# Power_28_10_15_v7.net
KiCad netlist of a schematic drawn in EAGLE
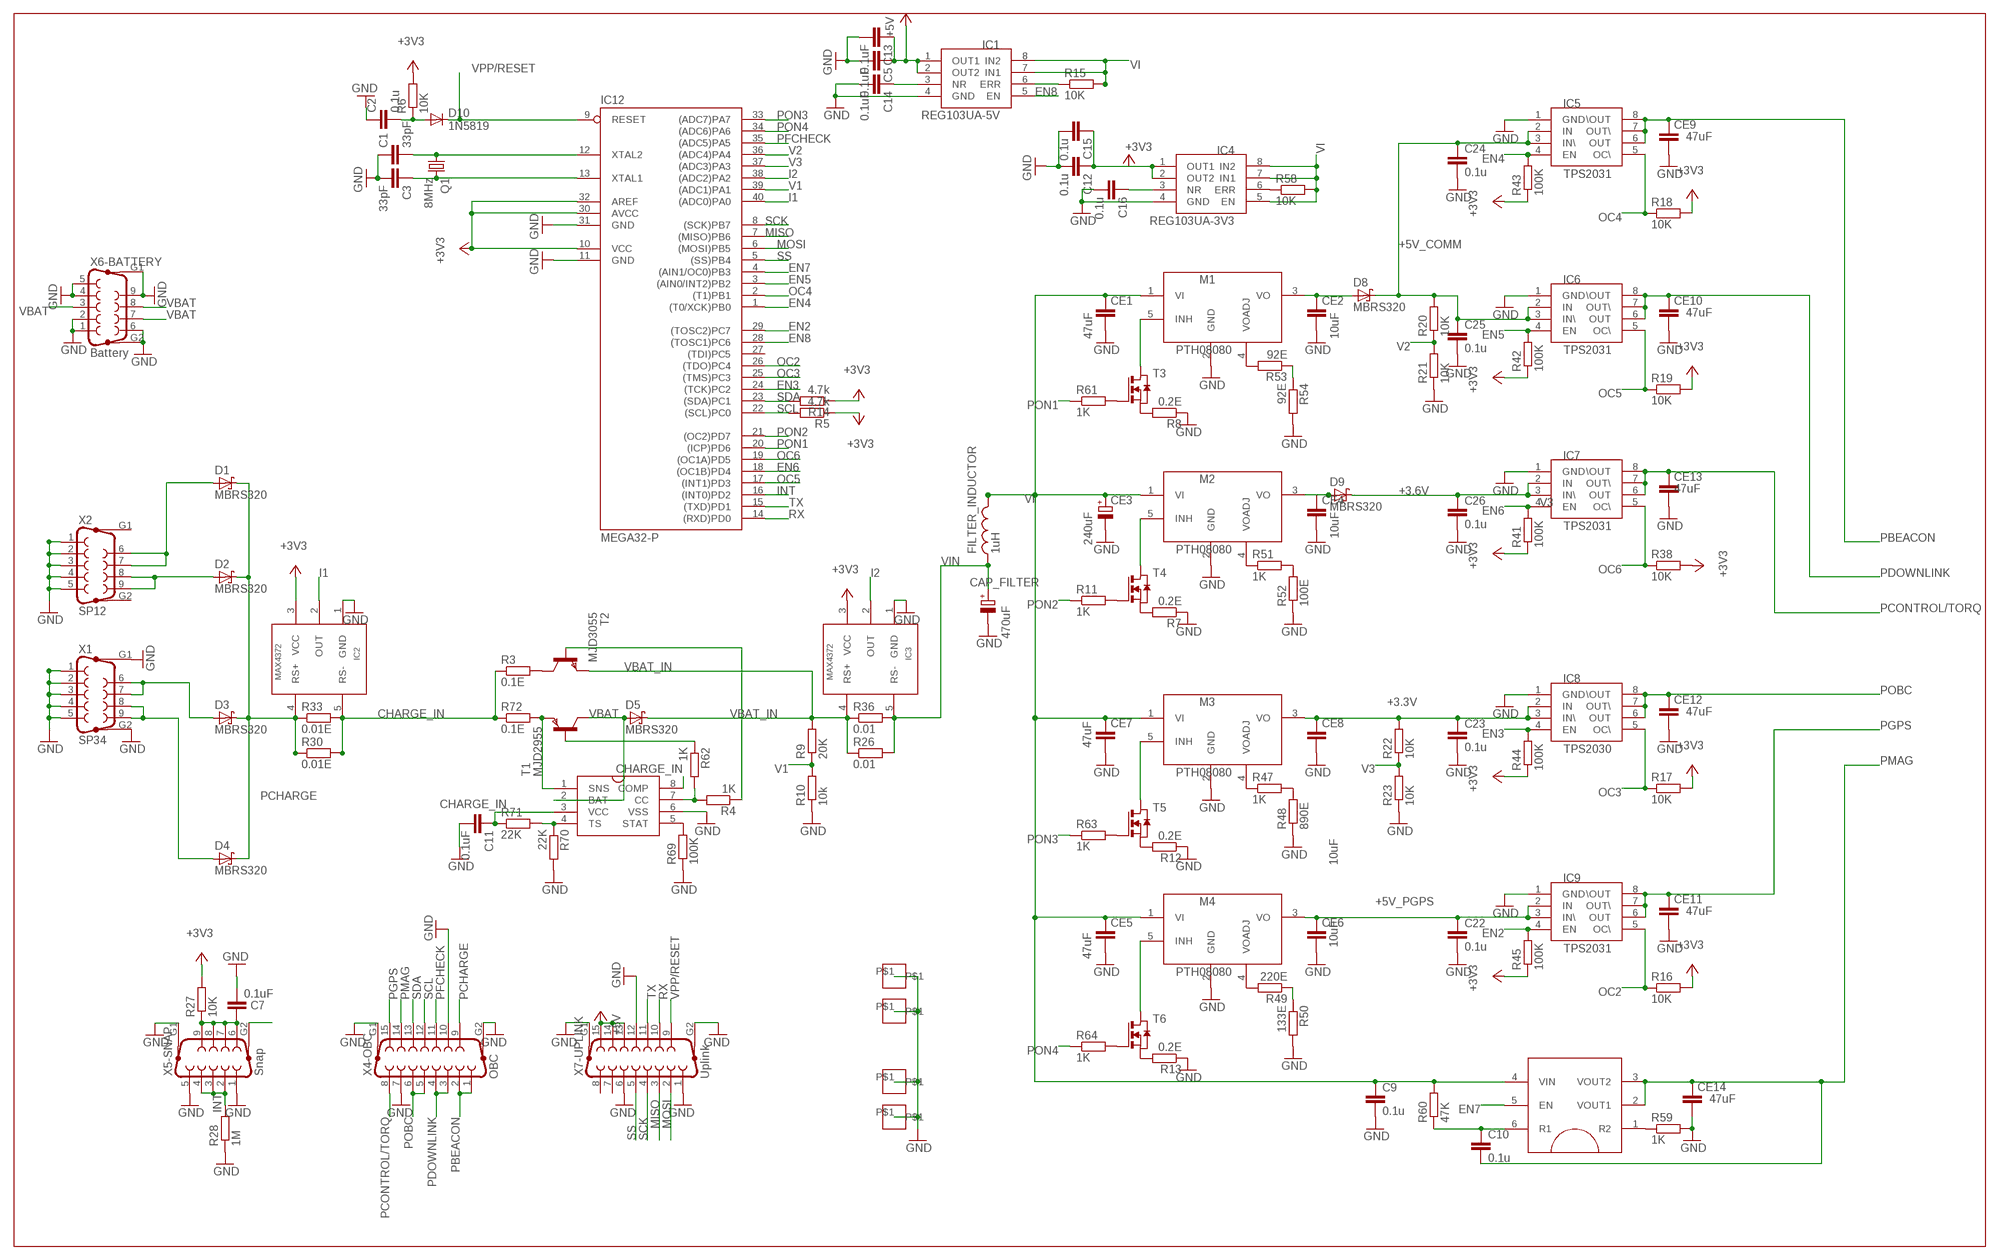
[diagram p0: schematic, sheet 1]

(export (version "E")
  (design (tool "Eeschema 10.0.6"))
  (components
    (comp (ref "C1")
      (value "33pF")
      (footprint "eagle-import:C1206")
      (libsource (lib "eagle-import") (part "C-EUC1206"))
    )
    (comp (ref "C2")
      (value "0.1u")
      (footprint "eagle-import:C1206")
      (libsource (lib "eagle-import") (part "C-EUC1206"))
    )
    (comp (ref "C3")
      (value "33pF")
      (footprint "eagle-import:C1206")
      (libsource (lib "eagle-import") (part "C-EUC1206"))
    )
    (comp (ref "C5")
      (value "0.1uF")
      (footprint "eagle-import:C1206")
      (libsource (lib "eagle-import") (part "C-EUC1206"))
    )
    (comp (ref "C7")
      (value "0.1uF")
      (footprint "eagle-import:C1206")
      (libsource (lib "eagle-import") (part "C-EUC1206"))
    )
    (comp (ref "C9")
      (value "0.1u")
      (footprint "eagle-import:C1206")
      (libsource (lib "eagle-import") (part "C-EUC1206"))
    )
    (comp (ref "C10")
      (value "0.1u")
      (footprint "eagle-import:C1206")
      (libsource (lib "eagle-import") (part "C-EUC1206"))
    )
    (comp (ref "C11")
      (value "0.1uF")
      (footprint "eagle-import:C1206")
      (libsource (lib "eagle-import") (part "C-EUC1206"))
    )
    (comp (ref "C12")
      (value "0.1u")
      (footprint "eagle-import:C1206")
      (libsource (lib "eagle-import") (part "C-EUC1206"))
    )
    (comp (ref "C13")
      (value "0.1uF")
      (footprint "eagle-import:C1206")
      (libsource (lib "eagle-import") (part "C-EUC1206"))
    )
    (comp (ref "C14")
      (value "0.1uF")
      (footprint "eagle-import:C1206")
      (libsource (lib "eagle-import") (part "C-EUC1206"))
    )
    (comp (ref "C15")
      (value "0.1u")
      (footprint "eagle-import:C1206")
      (libsource (lib "eagle-import") (part "C-EUC1206"))
    )
    (comp (ref "C16")
      (value "0.1u")
      (footprint "eagle-import:C1206")
      (libsource (lib "eagle-import") (part "C-EUC1206"))
    )
    (comp (ref "C22")
      (value "0.1u")
      (footprint "eagle-import:C1206")
      (libsource (lib "eagle-import") (part "C-EUC1206"))
    )
    (comp (ref "C23")
      (value "0.1u")
      (footprint "eagle-import:C1206")
      (libsource (lib "eagle-import") (part "C-EUC1206"))
    )
    (comp (ref "C24")
      (value "0.1u")
      (footprint "eagle-import:C1206")
      (libsource (lib "eagle-import") (part "C-EUC1206"))
    )
    (comp (ref "C25")
      (value "0.1u")
      (footprint "eagle-import:C1206")
      (libsource (lib "eagle-import") (part "C-EUC1206"))
    )
    (comp (ref "C26")
      (value "0.1u")
      (footprint "eagle-import:C1206")
      (libsource (lib "eagle-import") (part "C-EUC1206"))
    )
    (comp (ref "CAP_FILTER")
      (value "470uF")
      (footprint "eagle-import:CAP-POL-T3")
      (libsource (lib "eagle-import") (part "CAP-POLT3"))
    )
    (comp (ref "CE1")
      (value "47uF")
      (footprint "eagle-import:C1206K")
      (libsource (lib "eagle-import") (part "C-EUC1206K"))
    )
    (comp (ref "CE2")
      (value "10uF")
      (footprint "eagle-import:C1206K")
      (libsource (lib "eagle-import") (part "C-EUC1206K"))
    )
    (comp (ref "CE3")
      (value "240uF")
      (footprint "eagle-import:CAP-POL-T2")
      (libsource (lib "eagle-import") (part "CAP-POLT2"))
    )
    (comp (ref "CE4")
      (value "10uF")
      (footprint "eagle-import:C1206K")
      (libsource (lib "eagle-import") (part "C-EUC1206K"))
    )
    (comp (ref "CE5")
      (value "47uF")
      (footprint "eagle-import:C1206K")
      (libsource (lib "eagle-import") (part "C-EUC1206K"))
    )
    (comp (ref "CE6")
      (value "10uF")
      (footprint "eagle-import:C1206K")
      (libsource (lib "eagle-import") (part "C-EUC1206K"))
    )
    (comp (ref "CE7")
      (value "47uF")
      (footprint "eagle-import:C1206K")
      (libsource (lib "eagle-import") (part "C-EUC1206K"))
    )
    (comp (ref "CE8")
      (value "10uF")
      (footprint "eagle-import:C1206K")
      (libsource (lib "eagle-import") (part "C-EUC1206K"))
    )
    (comp (ref "CE9")
      (value "47uF")
      (footprint "eagle-import:C1206K")
      (libsource (lib "eagle-import") (part "C-EUC1206K"))
    )
    (comp (ref "CE10")
      (value "47uF")
      (footprint "eagle-import:C1206K")
      (libsource (lib "eagle-import") (part "C-EUC1206K"))
    )
    (comp (ref "CE11")
      (value "47uF")
      (footprint "eagle-import:C1206K")
      (libsource (lib "eagle-import") (part "C-EUC1206K"))
    )
    (comp (ref "CE12")
      (value "47uF")
      (footprint "eagle-import:C1206K")
      (libsource (lib "eagle-import") (part "C-EUC1206K"))
    )
    (comp (ref "CE13")
      (value "47uF")
      (footprint "eagle-import:C1206K")
      (libsource (lib "eagle-import") (part "C-EUC1206K"))
    )
    (comp (ref "CE14")
      (value "47uF")
      (footprint "eagle-import:C1206K")
      (libsource (lib "eagle-import") (part "C-EUC1206K"))
    )
    (comp (ref "D1")
      (value "MBRS320")
      (footprint "eagle-import:DIODE")
      (libsource (lib "eagle-import") (part "MBRS320"))
    )
    (comp (ref "D2")
      (value "MBRS320")
      (footprint "eagle-import:DIODE")
      (libsource (lib "eagle-import") (part "MBRS320"))
    )
    (comp (ref "D3")
      (value "MBRS320")
      (footprint "eagle-import:DIODE")
      (libsource (lib "eagle-import") (part "MBRS320"))
    )
    (comp (ref "D4")
      (value "MBRS320")
      (footprint "eagle-import:DIODE")
      (libsource (lib "eagle-import") (part "MBRS320"))
    )
    (comp (ref "D5")
      (value "MBRS320")
      (footprint "eagle-import:DIODE")
      (libsource (lib "eagle-import") (part "MBRS320"))
    )
    (comp (ref "D8")
      (value "MBRS320")
      (footprint "eagle-import:DIODE")
      (libsource (lib "eagle-import") (part "MBRS320"))
    )
    (comp (ref "D9")
      (value "MBRS320")
      (footprint "eagle-import:DIODE")
      (libsource (lib "eagle-import") (part "MBRS320"))
    )
    (comp (ref "D10")
      (value "1N5819")
      (footprint "eagle-import:D-5")
      (libsource (lib "eagle-import") (part "DIODE-D-5"))
    )
    (comp (ref "FILTER_INDUCTOR")
      (value "1uH")
      (footprint "eagle-import:MSS1260")
      (libsource (lib "eagle-import") (part "MSS1260"))
    )
    (comp (ref "IC1")
      (value "REG103UA-5V")
      (footprint "eagle-import:SO8")
      (libsource (lib "eagle-import") (part "REG103UA-5"))
    )
    (comp (ref "IC2")
      (value "MAX4372")
      (footprint "eagle-import:SOT-23-5")
      (libsource (lib "eagle-import") (part "MAX4372"))
    )
    (comp (ref "IC3")
      (value "MAX4372")
      (footprint "eagle-import:SOT-23-5")
      (libsource (lib "eagle-import") (part "MAX4372"))
    )
    (comp (ref "IC4")
      (value "REG103UA-3V3")
      (footprint "eagle-import:SO8")
      (libsource (lib "eagle-import") (part "REG103UA-5"))
    )
    (comp (ref "IC5")
      (value "TPS2031")
      (footprint "eagle-import:SO-8")
      (libsource (lib "eagle-import") (part "TPS203X"))
    )
    (comp (ref "IC6")
      (value "TPS2031")
      (footprint "eagle-import:SO-8")
      (libsource (lib "eagle-import") (part "TPS203X"))
    )
    (comp (ref "IC7")
      (value "TPS2031")
      (footprint "eagle-import:SO-8")
      (libsource (lib "eagle-import") (part "TPS203X"))
    )
    (comp (ref "IC8")
      (value "TPS2030")
      (footprint "eagle-import:SO-8")
      (libsource (lib "eagle-import") (part "TPS203X"))
    )
    (comp (ref "IC9")
      (value "TPS2031")
      (footprint "eagle-import:SO-8")
      (libsource (lib "eagle-import") (part "TPS203X"))
    )
    (comp (ref "IC10")
      (value "FDC6324")
      (footprint "eagle-import:SUPER-SOT-6")
      (libsource (lib "eagle-import") (part "FDC6324"))
    )
    (comp (ref "IC11")
      (value "BO2057")
      (footprint "eagle-import:SOIC-8")
      (libsource (lib "eagle-import") (part "BO2057"))
    )
    (comp (ref "IC12")
      (value "MEGA32-P")
      (footprint "eagle-import:DIL40")
      (fields (field (name "MPN") "ATMEGA32-16PU"))
      (libsource (lib "eagle-import") (part "MEGA32-P"))
    )
    (comp (ref "M1")
      (value "PTH08080")
      (footprint "eagle-import:DIP-05")
      (libsource (lib "eagle-import") (part "PTH08080"))
    )
    (comp (ref "M2")
      (value "PTH08080")
      (footprint "eagle-import:DIP-05")
      (libsource (lib "eagle-import") (part "PTH08080"))
    )
    (comp (ref "M3")
      (value "PTH08080")
      (footprint "eagle-import:DIP-05")
      (libsource (lib "eagle-import") (part "PTH08080"))
    )
    (comp (ref "M4")
      (value "PTH08080")
      (footprint "eagle-import:DIP-05")
      (libsource (lib "eagle-import") (part "PTH08080"))
    )
    (comp (ref "Q1")
      (value "8MHz")
      (footprint "eagle-import:HC49_S")
      (libsource (lib "eagle-import") (part "CRYSTALHC49S"))
    )
    (comp (ref "R3")
      (value "0.1E")
      (footprint "eagle-import:R1206")
      (libsource (lib "eagle-import") (part "R-EU_R1206"))
    )
    (comp (ref "R4")
      (value "1K")
      (footprint "eagle-import:R1206")
      (libsource (lib "eagle-import") (part "R-EU_R1206"))
    )
    (comp (ref "R5")
      (value "4.7k")
      (footprint "eagle-import:R1206")
      (libsource (lib "eagle-import") (part "R-EU_R1206"))
    )
    (comp (ref "R6")
      (value "10K")
      (footprint "eagle-import:R1206")
      (libsource (lib "eagle-import") (part "R-EU_R1206"))
    )
    (comp (ref "R7")
      (value "0.2E")
      (footprint "eagle-import:R1206")
      (libsource (lib "eagle-import") (part "R-EU_R1206"))
    )
    (comp (ref "R8")
      (value "0.2E")
      (footprint "eagle-import:R1206")
      (libsource (lib "eagle-import") (part "R-EU_R1206"))
    )
    (comp (ref "R9")
      (value "20K")
      (footprint "eagle-import:R1206")
      (libsource (lib "eagle-import") (part "R-EU_R1206"))
    )
    (comp (ref "R10")
      (value "10k")
      (footprint "eagle-import:R1206")
      (libsource (lib "eagle-import") (part "R-EU_R1206"))
    )
    (comp (ref "R11")
      (value "1K")
      (footprint "eagle-import:R1206")
      (libsource (lib "eagle-import") (part "R-EU_R1206"))
    )
    (comp (ref "R12")
      (value "0.2E")
      (footprint "eagle-import:R1206")
      (libsource (lib "eagle-import") (part "R-EU_R1206"))
    )
    (comp (ref "R13")
      (value "0.2E")
      (footprint "eagle-import:R1206")
      (libsource (lib "eagle-import") (part "R-EU_R1206"))
    )
    (comp (ref "R14")
      (value "4.7k")
      (footprint "eagle-import:R1206")
      (libsource (lib "eagle-import") (part "R-EU_R1206"))
    )
    (comp (ref "R15")
      (value "10K")
      (footprint "eagle-import:R1206")
      (libsource (lib "eagle-import") (part "R-EU_R1206"))
    )
    (comp (ref "R16")
      (value "10K")
      (footprint "eagle-import:R1206")
      (libsource (lib "eagle-import") (part "R-EU_R1206"))
    )
    (comp (ref "R17")
      (value "10K")
      (footprint "eagle-import:R1206")
      (libsource (lib "eagle-import") (part "R-EU_R1206"))
    )
    (comp (ref "R18")
      (value "10K")
      (footprint "eagle-import:R1206")
      (libsource (lib "eagle-import") (part "R-EU_R1206"))
    )
    (comp (ref "R19")
      (value "10K")
      (footprint "eagle-import:R1206")
      (libsource (lib "eagle-import") (part "R-EU_R1206"))
    )
    (comp (ref "R20")
      (value "10K")
      (footprint "eagle-import:R1206")
      (libsource (lib "eagle-import") (part "R-EU_R1206"))
    )
    (comp (ref "R21")
      (value "10K")
      (footprint "eagle-import:R1206")
      (libsource (lib "eagle-import") (part "R-EU_R1206"))
    )
    (comp (ref "R22")
      (value "10K")
      (footprint "eagle-import:R1206")
      (libsource (lib "eagle-import") (part "R-EU_R1206"))
    )
    (comp (ref "R23")
      (value "10K")
      (footprint "eagle-import:R1206")
      (libsource (lib "eagle-import") (part "R-EU_R1206"))
    )
    (comp (ref "R26")
      (value "0.01")
      (footprint "eagle-import:R1206")
      (libsource (lib "eagle-import") (part "R-EU_R1206"))
    )
    (comp (ref "R27")
      (value "10K")
      (footprint "eagle-import:R1206")
      (libsource (lib "eagle-import") (part "R-EU_R1206"))
    )
    (comp (ref "R28")
      (value "1M")
      (footprint "eagle-import:R1206")
      (libsource (lib "eagle-import") (part "R-EU_R1206"))
    )
    (comp (ref "R30")
      (value "0.01E")
      (footprint "eagle-import:R1206")
      (libsource (lib "eagle-import") (part "R-EU_R1206"))
    )
    (comp (ref "R33")
      (value "0.01E")
      (footprint "eagle-import:R1206")
      (libsource (lib "eagle-import") (part "R-EU_R1206"))
    )
    (comp (ref "R36")
      (value "0.01")
      (footprint "eagle-import:R1206")
      (libsource (lib "eagle-import") (part "R-EU_R1206"))
    )
    (comp (ref "R38")
      (value "10K")
      (footprint "eagle-import:R1206")
      (libsource (lib "eagle-import") (part "R-EU_R1206"))
    )
    (comp (ref "R41")
      (value "100K")
      (footprint "eagle-import:R1206")
      (libsource (lib "eagle-import") (part "R-EU_R1206"))
    )
    (comp (ref "R42")
      (value "100K")
      (footprint "eagle-import:R1206")
      (libsource (lib "eagle-import") (part "R-EU_R1206"))
    )
    (comp (ref "R43")
      (value "100K")
      (footprint "eagle-import:R1206")
      (libsource (lib "eagle-import") (part "R-EU_R1206"))
    )
    (comp (ref "R44")
      (value "100K")
      (footprint "eagle-import:R1206")
      (libsource (lib "eagle-import") (part "R-EU_R1206"))
    )
    (comp (ref "R45")
      (value "100K")
      (footprint "eagle-import:R1206")
      (libsource (lib "eagle-import") (part "R-EU_R1206"))
    )
    (comp (ref "R47")
      (value "1K")
      (footprint "eagle-import:R1206")
      (libsource (lib "eagle-import") (part "R-EU_R1206"))
    )
    (comp (ref "R48")
      (value "890E")
      (footprint "eagle-import:R1206")
      (libsource (lib "eagle-import") (part "R-EU_R1206"))
    )
    (comp (ref "R49")
      (value "220E")
      (footprint "eagle-import:R1206")
      (libsource (lib "eagle-import") (part "R-EU_R1206"))
    )
    (comp (ref "R50")
      (value "133E")
      (footprint "eagle-import:R1206")
      (libsource (lib "eagle-import") (part "R-EU_R1206"))
    )
    (comp (ref "R51")
      (value "1K")
      (footprint "eagle-import:R1206")
      (libsource (lib "eagle-import") (part "R-EU_R1206"))
    )
    (comp (ref "R52")
      (value "100E")
      (footprint "eagle-import:R1206")
      (libsource (lib "eagle-import") (part "R-EU_R1206"))
    )
    (comp (ref "R53")
      (value "92E")
      (footprint "eagle-import:R1206")
      (libsource (lib "eagle-import") (part "R-EU_R1206"))
    )
    (comp (ref "R54")
      (value "92E")
      (footprint "eagle-import:R1206")
      (libsource (lib "eagle-import") (part "R-EU_R1206"))
    )
    (comp (ref "R58")
      (value "10K")
      (footprint "eagle-import:R1206")
      (libsource (lib "eagle-import") (part "R-EU_R1206"))
    )
    (comp (ref "R59")
      (value "1K")
      (footprint "eagle-import:R1206")
      (libsource (lib "eagle-import") (part "R-EU_R1206"))
    )
    (comp (ref "R60")
      (value "47K")
      (footprint "eagle-import:R1206")
      (libsource (lib "eagle-import") (part "R-EU_R1206"))
    )
    (comp (ref "R61")
      (value "1K")
      (footprint "eagle-import:R1206")
      (libsource (lib "eagle-import") (part "R-EU_R1206"))
    )
    (comp (ref "R62")
      (value "1K")
      (footprint "eagle-import:R1206")
      (libsource (lib "eagle-import") (part "R-EU_R1206"))
    )
    (comp (ref "R63")
      (value "1K")
      (footprint "eagle-import:R1206")
      (libsource (lib "eagle-import") (part "R-EU_R1206"))
    )
    (comp (ref "R64")
      (value "1K")
      (footprint "eagle-import:R1206")
      (libsource (lib "eagle-import") (part "R-EU_R1206"))
    )
    (comp (ref "R69")
      (value "100K")
      (footprint "eagle-import:R1206")
      (libsource (lib "eagle-import") (part "R-EU_R1206"))
    )
    (comp (ref "R70")
      (value "22K")
      (footprint "eagle-import:R1206")
      (libsource (lib "eagle-import") (part "R-EU_R1206"))
    )
    (comp (ref "R71")
      (value "22K")
      (footprint "eagle-import:R1206")
      (libsource (lib "eagle-import") (part "R-EU_R1206"))
    )
    (comp (ref "R72")
      (value "0.1E")
      (footprint "eagle-import:R1206")
      (libsource (lib "eagle-import") (part "R-EU_R1206"))
    )
    (comp (ref "T1")
      (value "MJD2955")
      (footprint "eagle-import:DPAK-TO252")
      (libsource (lib "eagle-import") (part "MJD2955"))
    )
    (comp (ref "T2")
      (value "MJD3055")
      (footprint "eagle-import:DPAK-TO252")
      (libsource (lib "eagle-import") (part "MJD3055"))
    )
    (comp (ref "T3")
      (value "NMOSSOT23")
      (footprint "eagle-import:SOT-23")
      (libsource (lib "eagle-import") (part "NMOSSOT23"))
    )
    (comp (ref "T4")
      (value "NMOSSOT23")
      (footprint "eagle-import:SOT-23")
      (libsource (lib "eagle-import") (part "NMOSSOT23"))
    )
    (comp (ref "T5")
      (value "NMOSSOT23")
      (footprint "eagle-import:SOT-23")
      (libsource (lib "eagle-import") (part "NMOSSOT23"))
    )
    (comp (ref "T6")
      (value "NMOSSOT23")
      (footprint "eagle-import:SOT-23")
      (libsource (lib "eagle-import") (part "NMOSSOT23"))
    )
    (comp (ref "U$4")
      (value "MOUNT_SQ")
      (footprint "eagle-import:MOUNT_10MM")
      (libsource (lib "eagle-import") (part "MOUNT_SQ"))
    )
    (comp (ref "U$16")
      (value "MOUNT_SQ")
      (footprint "eagle-import:MOUNT_10MM")
      (libsource (lib "eagle-import") (part "MOUNT_SQ"))
    )
    (comp (ref "U$18")
      (value "MOUNT_SQ")
      (footprint "eagle-import:MOUNT_10MM")
      (libsource (lib "eagle-import") (part "MOUNT_SQ"))
    )
    (comp (ref "U$19")
      (value "MOUNT_SQ")
      (footprint "eagle-import:MOUNT_10MM")
      (libsource (lib "eagle-import") (part "MOUNT_SQ"))
    )
    (comp (ref "X1")
      (value "SP34")
      (footprint "eagle-import:F09HP")
      (libsource (lib "eagle-import") (part "F09HP"))
    )
    (comp (ref "X2")
      (value "SP12")
      (footprint "eagle-import:F09HP")
      (libsource (lib "eagle-import") (part "F09HP"))
    )
    (comp (ref "X4-OBC")
      (value "OBC")
      (footprint "eagle-import:F15HP")
      (libsource (lib "eagle-import") (part "F15HP"))
    )
    (comp (ref "X5-SNAP")
      (value "Snap")
      (footprint "eagle-import:F09HP")
      (libsource (lib "eagle-import") (part "satellite_F09HP"))
    )
    (comp (ref "X6-BATTERY")
      (value "Battery")
      (footprint "eagle-import:F09HP")
      (libsource (lib "eagle-import") (part "satellite_F09HP"))
    )
    (comp (ref "X7-UPLINK")
      (value "Uplink")
      (footprint "eagle-import:F15HP")
      (libsource (lib "eagle-import") (part "F15HP"))
    )
  )
  (nets
    (net (code "1") (name "+3V3") (class "Default")
      (node (ref "C12") (pin "1") (pinfunction "1_1") (pintype "passive"))
      (node (ref "C15") (pin "1") (pinfunction "1_1") (pintype "passive"))
      (node (ref "IC12") (pin "10") (pinfunction "VCC_10") (pintype "power_in"))
      (node (ref "IC12") (pin "30") (pinfunction "AVCC_30") (pintype "power_in"))
      (node (ref "IC12") (pin "32") (pinfunction "AREF_32") (pintype "passive"))
      (node (ref "IC2") (pin "3") (pinfunction "VCC_3") (pintype "bidirectional"))
      (node (ref "IC3") (pin "3") (pinfunction "VCC_3") (pintype "bidirectional"))
      (node (ref "IC4") (pin "1") (pinfunction "OUT1_1") (pintype "power_in"))
      (node (ref "IC4") (pin "2") (pinfunction "OUT2_2") (pintype "power_in"))
      (node (ref "R14") (pin "1") (pinfunction "1_1") (pintype "passive"))
      (node (ref "R16") (pin "2") (pinfunction "2_2") (pintype "passive"))
      (node (ref "R17") (pin "2") (pinfunction "2_2") (pintype "passive"))
      (node (ref "R18") (pin "2") (pinfunction "2_2") (pintype "passive"))
      (node (ref "R19") (pin "2") (pinfunction "2_2") (pintype "passive"))
      (node (ref "R27") (pin "2") (pinfunction "2_2") (pintype "passive"))
      (node (ref "R38") (pin "2") (pinfunction "2_2") (pintype "passive"))
      (node (ref "R41") (pin "1") (pinfunction "1_1") (pintype "passive"))
      (node (ref "R42") (pin "1") (pinfunction "1_1") (pintype "passive"))
      (node (ref "R43") (pin "1") (pinfunction "1_1") (pintype "passive"))
      (node (ref "R44") (pin "1") (pinfunction "1_1") (pintype "passive"))
      (node (ref "R45") (pin "1") (pinfunction "1_1") (pintype "passive"))
      (node (ref "R5") (pin "1") (pinfunction "1_1") (pintype "passive"))
      (node (ref "R6") (pin "2") (pinfunction "2_2") (pintype "passive"))
    )
    (net (code "2") (name "+5V") (class "Default")
      (node (ref "C13") (pin "1") (pinfunction "1_1") (pintype "passive"))
      (node (ref "C5") (pin "1") (pinfunction "1_1") (pintype "passive"))
      (node (ref "IC1") (pin "1") (pinfunction "OUT1_1") (pintype "power_in"))
      (node (ref "IC1") (pin "2") (pinfunction "OUT2_2") (pintype "power_in"))
      (node (ref "X7-UPLINK") (pin "13") (pinfunction "13_13") (pintype "passive"))
      (node (ref "X7-UPLINK") (pin "14") (pinfunction "14_14") (pintype "passive"))
      (node (ref "X7-UPLINK") (pin "15") (pinfunction "15_15") (pintype "passive"))
    )
    (net (code "3") (name "/+3.3V") (class "Default")
      (node (ref "C23") (pin "1") (pinfunction "1_1") (pintype "passive"))
      (node (ref "CE8") (pin "1") (pinfunction "1_1") (pintype "passive"))
      (node (ref "IC8") (pin "2") (pinfunction "IN_2") (pintype "power_in"))
      (node (ref "IC8") (pin "3") (pinfunction "IN\\_3") (pintype "power_in"))
      (node (ref "M3") (pin "3") (pinfunction "VO_3") (pintype "bidirectional"))
      (node (ref "R22") (pin "2") (pinfunction "2_2") (pintype "passive"))
    )
    (net (code "4") (name "/+3.6V") (class "Default")
      (node (ref "C26") (pin "1") (pinfunction "1_1") (pintype "passive"))
      (node (ref "D9") (pin "C") (pinfunction "C_C") (pintype "passive"))
      (node (ref "IC7") (pin "2") (pinfunction "IN_2") (pintype "power_in"))
      (node (ref "IC7") (pin "3") (pinfunction "IN\\_3") (pintype "power_in"))
    )
    (net (code "5") (name "/+5V_COMM") (class "Default")
      (node (ref "C24") (pin "1") (pinfunction "1_1") (pintype "passive"))
      (node (ref "C25") (pin "1") (pinfunction "1_1") (pintype "passive"))
      (node (ref "D8") (pin "C") (pinfunction "C_C") (pintype "passive"))
      (node (ref "IC5") (pin "2") (pinfunction "IN_2") (pintype "power_in"))
      (node (ref "IC5") (pin "3") (pinfunction "IN\\_3") (pintype "power_in"))
      (node (ref "IC6") (pin "2") (pinfunction "IN_2") (pintype "power_in"))
      (node (ref "IC6") (pin "3") (pinfunction "IN\\_3") (pintype "power_in"))
      (node (ref "R20") (pin "2") (pinfunction "2_2") (pintype "passive"))
    )
    (net (code "6") (name "/+5V_PGPS") (class "Default")
      (node (ref "C22") (pin "1") (pinfunction "1_1") (pintype "passive"))
      (node (ref "CE6") (pin "1") (pinfunction "1_1") (pintype "passive"))
      (node (ref "IC9") (pin "2") (pinfunction "IN_2") (pintype "power_in"))
      (node (ref "IC9") (pin "3") (pinfunction "IN\\_3") (pintype "power_in"))
      (node (ref "M4") (pin "3") (pinfunction "VO_3") (pintype "bidirectional"))
    )
    (net (code "7") (name "/CHARGE_IN") (class "Default")
      (node (ref "C11") (pin "1") (pinfunction "1_1") (pintype "passive"))
      (node (ref "IC11") (pin "3") (pinfunction "VCC_3") (pintype "power_in"))
      (node (ref "IC11") (pin "8") (pinfunction "COMP_8") (pintype "bidirectional"))
      (node (ref "IC2") (pin "5") (pinfunction "RS-_5") (pintype "bidirectional"))
      (node (ref "R3") (pin "1") (pinfunction "1_1") (pintype "passive"))
      (node (ref "R30") (pin "2") (pinfunction "2_2") (pintype "passive"))
      (node (ref "R33") (pin "2") (pinfunction "2_2") (pintype "passive"))
      (node (ref "R71") (pin "1") (pinfunction "1_1") (pintype "passive"))
      (node (ref "R72") (pin "1") (pinfunction "1_1") (pintype "passive"))
    )
    (net (code "8") (name "/EN2") (class "Default")
      (node (ref "IC12") (pin "29") (pinfunction "(TOSC2)PC7_29") (pintype "bidirectional"))
      (node (ref "IC9") (pin "4") (pinfunction "EN_4") (pintype "bidirectional"))
      (node (ref "R45") (pin "2") (pinfunction "2_2") (pintype "passive"))
    )
    (net (code "9") (name "/EN3") (class "Default")
      (node (ref "IC12") (pin "24") (pinfunction "(TCK)PC2_24") (pintype "bidirectional"))
      (node (ref "IC8") (pin "4") (pinfunction "EN_4") (pintype "bidirectional"))
      (node (ref "R44") (pin "2") (pinfunction "2_2") (pintype "passive"))
    )
    (net (code "10") (name "/EN4") (class "Default")
      (node (ref "IC12") (pin "1") (pinfunction "(T0/XCK)PB0_1") (pintype "bidirectional"))
      (node (ref "IC5") (pin "4") (pinfunction "EN_4") (pintype "bidirectional"))
      (node (ref "R43") (pin "2") (pinfunction "2_2") (pintype "passive"))
    )
    (net (code "11") (name "/EN5") (class "Default")
      (node (ref "IC12") (pin "3") (pinfunction "(AIN0/INT2)PB2_3") (pintype "bidirectional"))
      (node (ref "IC6") (pin "4") (pinfunction "EN_4") (pintype "bidirectional"))
      (node (ref "R42") (pin "2") (pinfunction "2_2") (pintype "passive"))
    )
    (net (code "12") (name "/EN6") (class "Default")
      (node (ref "IC12") (pin "18") (pinfunction "(OC1B)PD4_18") (pintype "bidirectional"))
      (node (ref "IC7") (pin "4") (pinfunction "EN_4") (pintype "bidirectional"))
      (node (ref "R41") (pin "2") (pinfunction "2_2") (pintype "passive"))
    )
    (net (code "13") (name "/EN7") (class "Default")
      (node (ref "IC10") (pin "5") (pinfunction "EN_5") (pintype "bidirectional"))
      (node (ref "IC12") (pin "4") (pinfunction "(AIN1/OC0)PB3_4") (pintype "bidirectional"))
    )
    (net (code "14") (name "/EN8") (class "Default")
      (node (ref "IC1") (pin "5") (pinfunction "EN_5") (pintype "bidirectional"))
      (node (ref "IC12") (pin "28") (pinfunction "(TOSC1)PC6_28") (pintype "bidirectional"))
    )
    (net (code "15") (name "/I1") (class "Default")
      (node (ref "IC12") (pin "40") (pinfunction "(ADC0)PA0_40") (pintype "bidirectional"))
      (node (ref "IC2") (pin "2") (pinfunction "OUT_2") (pintype "bidirectional"))
    )
    (net (code "16") (name "/I2") (class "Default")
      (node (ref "IC12") (pin "38") (pinfunction "(ADC2)PA2_38") (pintype "bidirectional"))
      (node (ref "IC3") (pin "2") (pinfunction "OUT_2") (pintype "bidirectional"))
    )
    (net (code "17") (name "/INT") (class "Default")
      (node (ref "IC12") (pin "16") (pinfunction "(INT0)PD2_16") (pintype "bidirectional"))
      (node (ref "R28") (pin "2") (pinfunction "2_2") (pintype "passive"))
      (node (ref "X5-SNAP") (pin "2") (pinfunction "2_2") (pintype "passive"))
      (node (ref "X5-SNAP") (pin "3") (pinfunction "3_3") (pintype "passive"))
      (node (ref "X5-SNAP") (pin "4") (pinfunction "4_4") (pintype "passive"))
    )
    (net (code "18") (name "/MISO") (class "Default")
      (node (ref "IC12") (pin "7") (pinfunction "(MISO)PB6_7") (pintype "bidirectional"))
      (node (ref "X7-UPLINK") (pin "3") (pinfunction "3_3") (pintype "passive"))
    )
    (net (code "19") (name "/MOSI") (class "Default")
      (node (ref "IC12") (pin "6") (pinfunction "(MOSI)PB5_6") (pintype "bidirectional"))
      (node (ref "X7-UPLINK") (pin "2") (pinfunction "2_2") (pintype "passive"))
    )
    (net (code "20") (name "/OC2") (class "Default")
      (node (ref "IC12") (pin "26") (pinfunction "(TDO)PC4_26") (pintype "bidirectional"))
      (node (ref "IC9") (pin "5") (pinfunction "OC\\_5") (pintype "bidirectional"))
      (node (ref "R16") (pin "1") (pinfunction "1_1") (pintype "passive"))
    )
    (net (code "21") (name "/OC3") (class "Default")
      (node (ref "IC12") (pin "25") (pinfunction "(TMS)PC3_25") (pintype "bidirectional"))
      (node (ref "IC8") (pin "5") (pinfunction "OC\\_5") (pintype "bidirectional"))
      (node (ref "R17") (pin "1") (pinfunction "1_1") (pintype "passive"))
    )
    (net (code "22") (name "/OC4") (class "Default")
      (node (ref "IC12") (pin "2") (pinfunction "(T1)PB1_2") (pintype "bidirectional"))
      (node (ref "IC5") (pin "5") (pinfunction "OC\\_5") (pintype "bidirectional"))
      (node (ref "R18") (pin "1") (pinfunction "1_1") (pintype "passive"))
    )
    (net (code "23") (name "/OC5") (class "Default")
      (node (ref "IC12") (pin "17") (pinfunction "(INT1)PD3_17") (pintype "bidirectional"))
      (node (ref "IC6") (pin "5") (pinfunction "OC\\_5") (pintype "bidirectional"))
      (node (ref "R19") (pin "1") (pinfunction "1_1") (pintype "passive"))
    )
    (net (code "24") (name "/OC6") (class "Default")
      (node (ref "IC12") (pin "19") (pinfunction "(OC1A)PD5_19") (pintype "bidirectional"))
      (node (ref "IC7") (pin "5") (pinfunction "OC\\_5") (pintype "bidirectional"))
      (node (ref "R38") (pin "1") (pinfunction "1_1") (pintype "passive"))
    )
    (net (code "25") (name "/PBEACON") (class "Default")
      (node (ref "CE9") (pin "1") (pinfunction "1_1") (pintype "passive"))
      (node (ref "IC5") (pin "6") (pinfunction "OUT_6") (pintype "power_in"))
      (node (ref "IC5") (pin "7") (pinfunction "OUT\\_7") (pintype "power_in"))
      (node (ref "IC5") (pin "8") (pinfunction "\\OUT_8") (pintype "power_in"))
      (node (ref "X4-OBC") (pin "1") (pinfunction "1_1") (pintype "passive"))
      (node (ref "X4-OBC") (pin "2") (pinfunction "2_2") (pintype "passive"))
    )
    (net (code "26") (name "/PCHARGE") (class "Default")
      (node (ref "D1") (pin "C") (pinfunction "C_C") (pintype "passive"))
      (node (ref "D2") (pin "C") (pinfunction "C_C") (pintype "passive"))
      (node (ref "D3") (pin "C") (pinfunction "C_C") (pintype "passive"))
      (node (ref "D4") (pin "C") (pinfunction "C_C") (pintype "passive"))
      (node (ref "IC2") (pin "4") (pinfunction "RS+_4") (pintype "bidirectional"))
      (node (ref "R30") (pin "1") (pinfunction "1_1") (pintype "passive"))
      (node (ref "R33") (pin "1") (pinfunction "1_1") (pintype "passive"))
      (node (ref "X4-OBC") (pin "9") (pinfunction "9_9") (pintype "passive"))
    )
    (net (code "27") (name "/PCONTROL{slash}TORQ") (class "Default")
      (node (ref "CE13") (pin "1") (pinfunction "1_1") (pintype "passive"))
      (node (ref "IC7") (pin "6") (pinfunction "OUT_6") (pintype "power_in"))
      (node (ref "IC7") (pin "7") (pinfunction "OUT\\_7") (pintype "power_in"))
      (node (ref "IC7") (pin "8") (pinfunction "\\OUT_8") (pintype "power_in"))
      (node (ref "X4-OBC") (pin "8") (pinfunction "8_8") (pintype "passive"))
    )
    (net (code "28") (name "/PDOWNLINK") (class "Default")
      (node (ref "CE10") (pin "1") (pinfunction "1_1") (pintype "passive"))
      (node (ref "IC6") (pin "6") (pinfunction "OUT_6") (pintype "power_in"))
      (node (ref "IC6") (pin "7") (pinfunction "OUT\\_7") (pintype "power_in"))
      (node (ref "IC6") (pin "8") (pinfunction "\\OUT_8") (pintype "power_in"))
      (node (ref "X4-OBC") (pin "3") (pinfunction "3_3") (pintype "passive"))
      (node (ref "X4-OBC") (pin "4") (pinfunction "4_4") (pintype "passive"))
    )
    (net (code "29") (name "/PFCHECK") (class "Default")
      (node (ref "IC12") (pin "35") (pinfunction "(ADC5)PA5_35") (pintype "bidirectional"))
      (node (ref "X4-OBC") (pin "11") (pinfunction "11_11") (pintype "passive"))
    )
    (net (code "30") (name "/PGPS") (class "Default")
      (node (ref "CE11") (pin "1") (pinfunction "1_1") (pintype "passive"))
      (node (ref "IC9") (pin "6") (pinfunction "OUT_6") (pintype "power_in"))
      (node (ref "IC9") (pin "7") (pinfunction "OUT\\_7") (pintype "power_in"))
      (node (ref "IC9") (pin "8") (pinfunction "\\OUT_8") (pintype "power_in"))
      (node (ref "X4-OBC") (pin "15") (pinfunction "15_15") (pintype "passive"))
    )
    (net (code "31") (name "/PMAG") (class "Default")
      (node (ref "C10") (pin "2") (pinfunction "2_2") (pintype "passive"))
      (node (ref "CE14") (pin "1") (pinfunction "1_1") (pintype "passive"))
      (node (ref "IC10") (pin "2") (pinfunction "VOUT1_2") (pintype "output"))
      (node (ref "IC10") (pin "3") (pinfunction "VOUT2_3") (pintype "output"))
      (node (ref "X4-OBC") (pin "14") (pinfunction "14_14") (pintype "passive"))
    )
    (net (code "32") (name "/POBC") (class "Default")
      (node (ref "CE12") (pin "1") (pinfunction "1_1") (pintype "passive"))
      (node (ref "IC8") (pin "6") (pinfunction "OUT_6") (pintype "power_in"))
      (node (ref "IC8") (pin "7") (pinfunction "OUT\\_7") (pintype "power_in"))
      (node (ref "IC8") (pin "8") (pinfunction "\\OUT_8") (pintype "power_in"))
      (node (ref "X4-OBC") (pin "5") (pinfunction "5_5") (pintype "passive"))
      (node (ref "X4-OBC") (pin "6") (pinfunction "6_6") (pintype "passive"))
    )
    (net (code "33") (name "/PON1") (class "Default")
      (node (ref "IC12") (pin "20") (pinfunction "(ICP)PD6_20") (pintype "bidirectional"))
      (node (ref "R61") (pin "1") (pinfunction "1_1") (pintype "passive"))
    )
    (net (code "34") (name "/PON2") (class "Default")
      (node (ref "IC12") (pin "21") (pinfunction "(OC2)PD7_21") (pintype "bidirectional"))
      (node (ref "R11") (pin "1") (pinfunction "1_1") (pintype "passive"))
    )
    (net (code "35") (name "/PON3") (class "Default")
      (node (ref "IC12") (pin "33") (pinfunction "(ADC7)PA7_33") (pintype "bidirectional"))
      (node (ref "R63") (pin "1") (pinfunction "1_1") (pintype "passive"))
    )
    (net (code "36") (name "/PON4") (class "Default")
      (node (ref "IC12") (pin "34") (pinfunction "(ADC6)PA6_34") (pintype "bidirectional"))
      (node (ref "R64") (pin "1") (pinfunction "1_1") (pintype "passive"))
    )
    (net (code "37") (name "/RX") (class "Default")
      (node (ref "IC12") (pin "14") (pinfunction "(RXD)PD0_14") (pintype "bidirectional"))
      (node (ref "X7-UPLINK") (pin "10") (pinfunction "10_10") (pintype "passive"))
    )
    (net (code "38") (name "/SCK") (class "Default")
      (node (ref "IC12") (pin "8") (pinfunction "(SCK)PB7_8") (pintype "bidirectional"))
      (node (ref "X7-UPLINK") (pin "4") (pinfunction "4_4") (pintype "passive"))
    )
    (net (code "39") (name "/SCL") (class "Default")
      (node (ref "IC12") (pin "22") (pinfunction "(SCL)PC0_22") (pintype "bidirectional"))
      (node (ref "R5") (pin "2") (pinfunction "2_2") (pintype "passive"))
      (node (ref "X4-OBC") (pin "12") (pinfunction "12_12") (pintype "passive"))
    )
    (net (code "40") (name "/SDA") (class "Default")
      (node (ref "IC12") (pin "23") (pinfunction "(SDA)PC1_23") (pintype "bidirectional"))
      (node (ref "R14") (pin "2") (pinfunction "2_2") (pintype "passive"))
      (node (ref "X4-OBC") (pin "13") (pinfunction "13_13") (pintype "passive"))
    )
    (net (code "41") (name "/SS") (class "Default")
      (node (ref "IC12") (pin "5") (pinfunction "(SS)PB4_5") (pintype "bidirectional"))
      (node (ref "X7-UPLINK") (pin "5") (pinfunction "5_5") (pintype "passive"))
    )
    (net (code "42") (name "/TX") (class "Default")
      (node (ref "IC12") (pin "15") (pinfunction "(TXD)PD1_15") (pintype "bidirectional"))
      (node (ref "X7-UPLINK") (pin "11") (pinfunction "11_11") (pintype "passive"))
    )
    (net (code "43") (name "/V1") (class "Default")
      (node (ref "IC12") (pin "39") (pinfunction "(ADC1)PA1_39") (pintype "bidirectional"))
      (node (ref "R10") (pin "2") (pinfunction "2_2") (pintype "passive"))
      (node (ref "R9") (pin "1") (pinfunction "1_1") (pintype "passive"))
    )
    (net (code "44") (name "/V2") (class "Default")
      (node (ref "IC12") (pin "36") (pinfunction "(ADC4)PA4_36") (pintype "bidirectional"))
      (node (ref "R20") (pin "1") (pinfunction "1_1") (pintype "passive"))
      (node (ref "R21") (pin "2") (pinfunction "2_2") (pintype "passive"))
    )
    (net (code "45") (name "/V3") (class "Default")
      (node (ref "IC12") (pin "37") (pinfunction "(ADC3)PA3_37") (pintype "bidirectional"))
      (node (ref "R22") (pin "1") (pinfunction "1_1") (pintype "passive"))
      (node (ref "R23") (pin "2") (pinfunction "2_2") (pintype "passive"))
    )
    (net (code "46") (name "/VBAT") (class "Default")
      (node (ref "D5") (pin "A") (pinfunction "A_A") (pintype "passive"))
      (node (ref "IC11") (pin "2") (pinfunction "BAT_2") (pintype "power_in"))
      (node (ref "T1") (pin "2") (pinfunction "C_2") (pintype "passive"))
      (node (ref "X6-BATTERY") (pin "3") (pinfunction "3_3") (pintype "passive"))
      (node (ref "X6-BATTERY") (pin "7") (pinfunction "7_7") (pintype "passive"))
      (node (ref "X6-BATTERY") (pin "8") (pinfunction "8_8") (pintype "passive"))
    )
    (net (code "47") (name "/VBAT_IN") (class "Default")
      (node (ref "D5") (pin "C") (pinfunction "C_C") (pintype "passive"))
      (node (ref "IC3") (pin "4") (pinfunction "RS+_4") (pintype "bidirectional"))
      (node (ref "R26") (pin "1") (pinfunction "1_1") (pintype "passive"))
      (node (ref "R36") (pin "1") (pinfunction "1_1") (pintype "passive"))
      (node (ref "R9") (pin "2") (pinfunction "2_2") (pintype "passive"))
      (node (ref "T2") (pin "3") (pinfunction "E_3") (pintype "passive"))
    )
    (net (code "48") (name "/VI") (class "Default")
      (node (ref "C9") (pin "1") (pinfunction "1_1") (pintype "passive"))
      (node (ref "CE1") (pin "1") (pinfunction "1_1") (pintype "passive"))
      (node (ref "CE3") (pin "P$1") (pinfunction "+_P$1") (pintype "passive"))
      (node (ref "CE5") (pin "1") (pinfunction "1_1") (pintype "passive"))
      (node (ref "CE7") (pin "1") (pinfunction "1_1") (pintype "passive"))
      (node (ref "FILTER_INDUCTOR") (pin "P$1") (pinfunction "P$1_P$1") (pintype "passive"))
      (node (ref "IC1") (pin "7") (pinfunction "IN1_7") (pintype "power_in"))
      (node (ref "IC1") (pin "8") (pinfunction "IN2_8") (pintype "power_in"))
      (node (ref "IC10") (pin "4") (pinfunction "VIN_4") (pintype "input"))
      (node (ref "IC4") (pin "5") (pinfunction "EN_5") (pintype "bidirectional"))
      (node (ref "IC4") (pin "7") (pinfunction "IN1_7") (pintype "power_in"))
      (node (ref "IC4") (pin "8") (pinfunction "IN2_8") (pintype "power_in"))
      (node (ref "M1") (pin "1") (pinfunction "VI_1") (pintype "bidirectional"))
      (node (ref "M2") (pin "1") (pinfunction "VI_1") (pintype "bidirectional"))
      (node (ref "M3") (pin "1") (pinfunction "VI_1") (pintype "bidirectional"))
      (node (ref "M4") (pin "1") (pinfunction "VI_1") (pintype "bidirectional"))
      (node (ref "R15") (pin "2") (pinfunction "2_2") (pintype "passive"))
      (node (ref "R58") (pin "2") (pinfunction "2_2") (pintype "passive"))
      (node (ref "R60") (pin "2") (pinfunction "2_2") (pintype "passive"))
    )
    (net (code "49") (name "/VIN") (class "Default")
      (node (ref "CAP_FILTER") (pin "P$1") (pinfunction "+_P$1") (pintype "passive"))
      (node (ref "FILTER_INDUCTOR") (pin "P$2") (pinfunction "P$2_P$2") (pintype "passive"))
      (node (ref "IC3") (pin "5") (pinfunction "RS-_5") (pintype "bidirectional"))
      (node (ref "R26") (pin "2") (pinfunction "2_2") (pintype "passive"))
      (node (ref "R36") (pin "2") (pinfunction "2_2") (pintype "passive"))
    )
    (net (code "50") (name "/VPP{slash}RESET") (class "Default")
      (node (ref "D10") (pin "C") (pinfunction "C_C") (pintype "passive"))
      (node (ref "IC12") (pin "9") (pinfunction "RESET_9") (pintype "input"))
      (node (ref "X7-UPLINK") (pin "9") (pinfunction "9_9") (pintype "passive"))
    )
    (net (code "51") (name "GND") (class "Default")
      (node (ref "C1") (pin "1") (pinfunction "1_1") (pintype "passive"))
      (node (ref "C11") (pin "2") (pinfunction "2_2") (pintype "passive"))
      (node (ref "C12") (pin "2") (pinfunction "2_2") (pintype "passive"))
      (node (ref "C13") (pin "2") (pinfunction "2_2") (pintype "passive"))
      (node (ref "C14") (pin "2") (pinfunction "2_2") (pintype "passive"))
      (node (ref "C15") (pin "2") (pinfunction "2_2") (pintype "passive"))
      (node (ref "C16") (pin "2") (pinfunction "2_2") (pintype "passive"))
      (node (ref "C2") (pin "1") (pinfunction "1_1") (pintype "passive"))
      (node (ref "C22") (pin "2") (pinfunction "2_2") (pintype "passive"))
      (node (ref "C23") (pin "2") (pinfunction "2_2") (pintype "passive"))
      (node (ref "C24") (pin "2") (pinfunction "2_2") (pintype "passive"))
      (node (ref "C25") (pin "2") (pinfunction "2_2") (pintype "passive"))
      (node (ref "C26") (pin "2") (pinfunction "2_2") (pintype "passive"))
      (node (ref "C3") (pin "2") (pinfunction "2_2") (pintype "passive"))
      (node (ref "C5") (pin "2") (pinfunction "2_2") (pintype "passive"))
      (node (ref "C7") (pin "2") (pinfunction "2_2") (pintype "passive"))
      (node (ref "C9") (pin "2") (pinfunction "2_2") (pintype "passive"))
      (node (ref "CAP_FILTER") (pin "P$2") (pinfunction "-_P$2") (pintype "passive"))
      (node (ref "CE1") (pin "2") (pinfunction "2_2") (pintype "passive"))
      (node (ref "CE10") (pin "2") (pinfunction "2_2") (pintype "passive"))
      (node (ref "CE11") (pin "2") (pinfunction "2_2") (pintype "passive"))
      (node (ref "CE12") (pin "2") (pinfunction "2_2") (pintype "passive"))
      (node (ref "CE13") (pin "2") (pinfunction "2_2") (pintype "passive"))
      (node (ref "CE14") (pin "2") (pinfunction "2_2") (pintype "passive"))
      (node (ref "CE2") (pin "2") (pinfunction "2_2") (pintype "passive"))
      (node (ref "CE3") (pin "P$2") (pinfunction "-_P$2") (pintype "passive"))
      (node (ref "CE4") (pin "2") (pinfunction "2_2") (pintype "passive"))
      (node (ref "CE5") (pin "2") (pinfunction "2_2") (pintype "passive"))
      (node (ref "CE6") (pin "2") (pinfunction "2_2") (pintype "passive"))
      (node (ref "CE7") (pin "2") (pinfunction "2_2") (pintype "passive"))
      (node (ref "CE8") (pin "2") (pinfunction "2_2") (pintype "passive"))
      (node (ref "CE9") (pin "2") (pinfunction "2_2") (pintype "passive"))
      (node (ref "IC1") (pin "4") (pinfunction "GND_4") (pintype "power_in"))
      (node (ref "IC11") (pin "6") (pinfunction "VSS_6") (pintype "power_in"))
      (node (ref "IC12") (pin "11") (pinfunction "GND_11") (pintype "power_in"))
      (node (ref "IC12") (pin "31") (pinfunction "GND_31") (pintype "power_in"))
      (node (ref "IC2") (pin "1") (pinfunction "GND_1") (pintype "bidirectional"))
      (node (ref "IC3") (pin "1") (pinfunction "GND_1") (pintype "bidirectional"))
      (node (ref "IC4") (pin "4") (pinfunction "GND_4") (pintype "power_in"))
      (node (ref "IC5") (pin "1") (pinfunction "GND_1") (pintype "power_in"))
      (node (ref "IC6") (pin "1") (pinfunction "GND_1") (pintype "power_in"))
      (node (ref "IC7") (pin "1") (pinfunction "GND_1") (pintype "power_in"))
      (node (ref "IC8") (pin "1") (pinfunction "GND_1") (pintype "power_in"))
      (node (ref "IC9") (pin "1") (pinfunction "GND_1") (pintype "power_in"))
      (node (ref "M1") (pin "2") (pinfunction "GND_2") (pintype "bidirectional"))
      (node (ref "M2") (pin "2") (pinfunction "GND_2") (pintype "bidirectional"))
      (node (ref "M3") (pin "2") (pinfunction "GND_2") (pintype "bidirectional"))
      (node (ref "M4") (pin "2") (pinfunction "GND_2") (pintype "bidirectional"))
      (node (ref "R10") (pin "1") (pinfunction "1_1") (pintype "passive"))
      (node (ref "R12") (pin "1") (pinfunction "1_1") (pintype "passive"))
      (node (ref "R13") (pin "1") (pinfunction "1_1") (pintype "passive"))
      (node (ref "R21") (pin "1") (pinfunction "1_1") (pintype "passive"))
      (node (ref "R23") (pin "1") (pinfunction "1_1") (pintype "passive"))
      (node (ref "R28") (pin "1") (pinfunction "1_1") (pintype "passive"))
      (node (ref "R48") (pin "1") (pinfunction "1_1") (pintype "passive"))
      (node (ref "R50") (pin "2") (pinfunction "2_2") (pintype "passive"))
      (node (ref "R52") (pin "1") (pinfunction "1_1") (pintype "passive"))
      (node (ref "R54") (pin "2") (pinfunction "2_2") (pintype "passive"))
      (node (ref "R59") (pin "2") (pinfunction "2_2") (pintype "passive"))
      (node (ref "R69") (pin "1") (pinfunction "1_1") (pintype "passive"))
      (node (ref "R7") (pin "1") (pinfunction "1_1") (pintype "passive"))
      (node (ref "R70") (pin "2") (pinfunction "2_2") (pintype "passive"))
      (node (ref "R8") (pin "1") (pinfunction "1_1") (pintype "passive"))
      (node (ref "U$16") (pin "P$1") (pinfunction "P$1_P$1") (pintype "power_in"))
      (node (ref "U$18") (pin "P$1") (pinfunction "P$1_P$1") (pintype "power_in"))
      (node (ref "U$19") (pin "P$1") (pinfunction "P$1_P$1") (pintype "power_in"))
      (node (ref "U$4") (pin "P$1") (pinfunction "P$1_P$1") (pintype "power_in"))
      (node (ref "X1") (pin "1") (pinfunction "1_1") (pintype "passive"))
      (node (ref "X1") (pin "2") (pinfunction "2_2") (pintype "passive"))
      (node (ref "X1") (pin "3") (pinfunction "3_3") (pintype "passive"))
      (node (ref "X1") (pin "4") (pinfunction "4_4") (pintype "passive"))
      (node (ref "X1") (pin "5") (pinfunction "5_5") (pintype "passive"))
      (node (ref "X1") (pin "G1") (pinfunction "G1_G1") (pintype "passive"))
      (node (ref "X1") (pin "G2") (pinfunction "G2_G2") (pintype "passive"))
      (node (ref "X2") (pin "1") (pinfunction "1_1") (pintype "passive"))
      (node (ref "X2") (pin "2") (pinfunction "2_2") (pintype "passive"))
      (node (ref "X2") (pin "3") (pinfunction "3_3") (pintype "passive"))
      (node (ref "X2") (pin "4") (pinfunction "4_4") (pintype "passive"))
      (node (ref "X2") (pin "5") (pinfunction "5_5") (pintype "passive"))
      (node (ref "X4-OBC") (pin "10") (pinfunction "10_10") (pintype "passive"))
      (node (ref "X4-OBC") (pin "7") (pinfunction "7_7") (pintype "passive"))
      (node (ref "X4-OBC") (pin "G1") (pinfunction "G1_G1") (pintype "passive"))
      (node (ref "X4-OBC") (pin "G2") (pinfunction "G2_G2") (pintype "passive"))
      (node (ref "X5-SNAP") (pin "1") (pinfunction "1_1") (pintype "passive"))
      (node (ref "X5-SNAP") (pin "5") (pinfunction "5_5") (pintype "passive"))
      (node (ref "X5-SNAP") (pin "G1") (pinfunction "G1_G1") (pintype "passive"))
      (node (ref "X5-SNAP") (pin "G2") (pinfunction "G2_G2") (pintype "passive"))
      (node (ref "X6-BATTERY") (pin "1") (pinfunction "1_1") (pintype "passive"))
      (node (ref "X6-BATTERY") (pin "2") (pinfunction "2_2") (pintype "passive"))
      (node (ref "X6-BATTERY") (pin "4") (pinfunction "4_4") (pintype "passive"))
      (node (ref "X6-BATTERY") (pin "5") (pinfunction "5_5") (pintype "passive"))
      (node (ref "X6-BATTERY") (pin "6") (pinfunction "6_6") (pintype "passive"))
      (node (ref "X6-BATTERY") (pin "9") (pinfunction "9_9") (pintype "passive"))
      (node (ref "X6-BATTERY") (pin "G1") (pinfunction "G1_G1") (pintype "passive"))
      (node (ref "X6-BATTERY") (pin "G2") (pinfunction "G2_G2") (pintype "passive"))
      (node (ref "X7-UPLINK") (pin "1") (pinfunction "1_1") (pintype "passive"))
      (node (ref "X7-UPLINK") (pin "12") (pinfunction "12_12") (pintype "passive"))
      (node (ref "X7-UPLINK") (pin "6") (pinfunction "6_6") (pintype "passive"))
      (node (ref "X7-UPLINK") (pin "G1") (pinfunction "G1_G1") (pintype "passive"))
      (node (ref "X7-UPLINK") (pin "G2") (pinfunction "G2_G2") (pintype "passive"))
    )
    (net (code "52") (name "Net-(C2-Pad2)") (class "Default")
      (node (ref "C2") (pin "2") (pinfunction "2_2") (pintype "passive"))
      (node (ref "D10") (pin "A") (pinfunction "A_A") (pintype "passive"))
      (node (ref "R6") (pin "1") (pinfunction "1_1") (pintype "passive"))
    )
    (net (code "53") (name "Net-(C7-Pad1)") (class "Default")
      (node (ref "C7") (pin "1") (pinfunction "1_1") (pintype "passive"))
      (node (ref "R27") (pin "1") (pinfunction "1_1") (pintype "passive"))
      (node (ref "X5-SNAP") (pin "6") (pinfunction "6_6") (pintype "passive"))
      (node (ref "X5-SNAP") (pin "7") (pinfunction "7_7") (pintype "passive"))
      (node (ref "X5-SNAP") (pin "8") (pinfunction "8_8") (pintype "passive"))
      (node (ref "X5-SNAP") (pin "9") (pinfunction "9_9") (pintype "passive"))
    )
    (net (code "54") (name "Net-(D1-PadA)") (class "Default")
      (node (ref "D1") (pin "A") (pinfunction "A_A") (pintype "passive"))
      (node (ref "X2") (pin "6") (pinfunction "6_6") (pintype "passive"))
      (node (ref "X2") (pin "7") (pinfunction "7_7") (pintype "passive"))
    )
    (net (code "55") (name "Net-(D2-PadA)") (class "Default")
      (node (ref "D2") (pin "A") (pinfunction "A_A") (pintype "passive"))
      (node (ref "X2") (pin "8") (pinfunction "8_8") (pintype "passive"))
      (node (ref "X2") (pin "9") (pinfunction "9_9") (pintype "passive"))
    )
    (net (code "56") (name "Net-(D3-PadA)") (class "Default")
      (node (ref "D3") (pin "A") (pinfunction "A_A") (pintype "passive"))
      (node (ref "X1") (pin "6") (pinfunction "6_6") (pintype "passive"))
      (node (ref "X1") (pin "7") (pinfunction "7_7") (pintype "passive"))
    )
    (net (code "57") (name "Net-(D4-PadA)") (class "Default")
      (node (ref "D4") (pin "A") (pinfunction "A_A") (pintype "passive"))
      (node (ref "X1") (pin "8") (pinfunction "8_8") (pintype "passive"))
      (node (ref "X1") (pin "9") (pinfunction "9_9") (pintype "passive"))
    )
    (net (code "58") (name "Net-(IC1-ERR)") (class "Default")
      (node (ref "IC1") (pin "6") (pinfunction "ERR_6") (pintype "bidirectional"))
      (node (ref "R15") (pin "1") (pinfunction "1_1") (pintype "passive"))
    )
    (net (code "59") (name "Net-(IC1-NR)") (class "Default")
      (node (ref "C14") (pin "1") (pinfunction "1_1") (pintype "passive"))
      (node (ref "IC1") (pin "3") (pinfunction "NR_3") (pintype "bidirectional"))
    )
    (net (code "60") (name "Net-(IC4-ERR)") (class "Default")
      (node (ref "IC4") (pin "6") (pinfunction "ERR_6") (pintype "bidirectional"))
      (node (ref "R58") (pin "1") (pinfunction "1_1") (pintype "passive"))
    )
    (net (code "61") (name "Net-(IC4-NR)") (class "Default")
      (node (ref "C16") (pin "1") (pinfunction "1_1") (pintype "passive"))
      (node (ref "IC4") (pin "3") (pinfunction "NR_3") (pintype "bidirectional"))
    )
    (net (code "62") (name "Net-(IC10-R1)") (class "Default")
      (node (ref "C10") (pin "1") (pinfunction "1_1") (pintype "passive"))
      (node (ref "IC10") (pin "6") (pinfunction "R1_6") (pintype "bidirectional"))
      (node (ref "R60") (pin "1") (pinfunction "1_1") (pintype "passive"))
    )
    (net (code "63") (name "Net-(IC10-R2)") (class "Default")
      (node (ref "IC10") (pin "1") (pinfunction "R2_1") (pintype "bidirectional"))
      (node (ref "R59") (pin "1") (pinfunction "1_1") (pintype "passive"))
    )
    (net (code "64") (name "Net-(IC11-CC)") (class "Default")
      (node (ref "IC11") (pin "7") (pinfunction "CC_7") (pintype "bidirectional"))
      (node (ref "R4") (pin "2") (pinfunction "2_2") (pintype "passive"))
      (node (ref "R62") (pin "2") (pinfunction "2_2") (pintype "passive"))
    )
    (net (code "65") (name "Net-(IC11-SNS)") (class "Default")
      (node (ref "IC11") (pin "1") (pinfunction "SNS_1") (pintype "bidirectional"))
      (node (ref "R72") (pin "2") (pinfunction "2_2") (pintype "passive"))
      (node (ref "T1") (pin "3") (pinfunction "E_3") (pintype "passive"))
    )
    (net (code "66") (name "Net-(IC11-STAT)") (class "Default")
      (node (ref "IC11") (pin "5") (pinfunction "STAT_5") (pintype "bidirectional"))
      (node (ref "R69") (pin "2") (pinfunction "2_2") (pintype "passive"))
    )
    (net (code "67") (name "Net-(IC11-TS)") (class "Default")
      (node (ref "IC11") (pin "4") (pinfunction "TS_4") (pintype "bidirectional"))
      (node (ref "R70") (pin "1") (pinfunction "1_1") (pintype "passive"))
      (node (ref "R71") (pin "2") (pinfunction "2_2") (pintype "passive"))
    )
    (net (code "68") (name "Net-(IC12-XTAL1)") (class "Default")
      (node (ref "C3") (pin "1") (pinfunction "1_1") (pintype "passive"))
      (node (ref "IC12") (pin "13") (pinfunction "XTAL1_13") (pintype "bidirectional"))
      (node (ref "Q1") (pin "2") (pinfunction "2_2") (pintype "passive"))
    )
    (net (code "69") (name "Net-(IC12-XTAL2)") (class "Default")
      (node (ref "C1") (pin "2") (pinfunction "2_2") (pintype "passive"))
      (node (ref "IC12") (pin "12") (pinfunction "XTAL2_12") (pintype "bidirectional"))
      (node (ref "Q1") (pin "1") (pinfunction "1_1") (pintype "passive"))
    )
    (net (code "70") (name "Net-(M1-INH)") (class "Default")
      (node (ref "M1") (pin "5") (pinfunction "INH_5") (pintype "bidirectional"))
      (node (ref "T3") (pin "1") (pinfunction "D_1") (pintype "passive"))
    )
    (net (code "71") (name "Net-(M1-VO)") (class "Default")
      (node (ref "CE2") (pin "1") (pinfunction "1_1") (pintype "passive"))
      (node (ref "D8") (pin "A") (pinfunction "A_A") (pintype "passive"))
      (node (ref "M1") (pin "3") (pinfunction "VO_3") (pintype "bidirectional"))
    )
    (net (code "72") (name "Net-(M1-VOADJ)") (class "Default")
      (node (ref "M1") (pin "4") (pinfunction "VOADJ_4") (pintype "bidirectional"))
      (node (ref "R53") (pin "2") (pinfunction "2_2") (pintype "passive"))
    )
    (net (code "73") (name "Net-(M2-INH)") (class "Default")
      (node (ref "M2") (pin "5") (pinfunction "INH_5") (pintype "bidirectional"))
      (node (ref "T4") (pin "1") (pinfunction "D_1") (pintype "passive"))
    )
    (net (code "74") (name "Net-(M2-VO)") (class "Default")
      (node (ref "CE4") (pin "1") (pinfunction "1_1") (pintype "passive"))
      (node (ref "D9") (pin "A") (pinfunction "A_A") (pintype "passive"))
      (node (ref "M2") (pin "3") (pinfunction "VO_3") (pintype "bidirectional"))
    )
    (net (code "75") (name "Net-(M2-VOADJ)") (class "Default")
      (node (ref "M2") (pin "4") (pinfunction "VOADJ_4") (pintype "bidirectional"))
      (node (ref "R51") (pin "1") (pinfunction "1_1") (pintype "passive"))
    )
    (net (code "76") (name "Net-(M3-INH)") (class "Default")
      (node (ref "M3") (pin "5") (pinfunction "INH_5") (pintype "bidirectional"))
      (node (ref "T5") (pin "1") (pinfunction "D_1") (pintype "passive"))
    )
    (net (code "77") (name "Net-(M3-VOADJ)") (class "Default")
      (node (ref "M3") (pin "4") (pinfunction "VOADJ_4") (pintype "bidirectional"))
      (node (ref "R47") (pin "1") (pinfunction "1_1") (pintype "passive"))
    )
    (net (code "78") (name "Net-(M4-INH)") (class "Default")
      (node (ref "M4") (pin "5") (pinfunction "INH_5") (pintype "bidirectional"))
      (node (ref "T6") (pin "1") (pinfunction "D_1") (pintype "passive"))
    )
    (net (code "79") (name "Net-(M4-VOADJ)") (class "Default")
      (node (ref "M4") (pin "4") (pinfunction "VOADJ_4") (pintype "bidirectional"))
      (node (ref "R49") (pin "2") (pinfunction "2_2") (pintype "passive"))
    )
    (net (code "80") (name "Net-(R47-Pad2)") (class "Default")
      (node (ref "R47") (pin "2") (pinfunction "2_2") (pintype "passive"))
      (node (ref "R48") (pin "2") (pinfunction "2_2") (pintype "passive"))
    )
    (net (code "81") (name "Net-(R49-Pad1)") (class "Default")
      (node (ref "R49") (pin "1") (pinfunction "1_1") (pintype "passive"))
      (node (ref "R50") (pin "1") (pinfunction "1_1") (pintype "passive"))
    )
    (net (code "82") (name "Net-(R51-Pad2)") (class "Default")
      (node (ref "R51") (pin "2") (pinfunction "2_2") (pintype "passive"))
      (node (ref "R52") (pin "2") (pinfunction "2_2") (pintype "passive"))
    )
    (net (code "83") (name "Net-(R53-Pad1)") (class "Default")
      (node (ref "R53") (pin "1") (pinfunction "1_1") (pintype "passive"))
      (node (ref "R54") (pin "1") (pinfunction "1_1") (pintype "passive"))
    )
    (net (code "84") (name "Net-(T1-B)") (class "Default")
      (node (ref "R62") (pin "1") (pinfunction "1_1") (pintype "passive"))
      (node (ref "T1") (pin "1") (pinfunction "B_1") (pintype "passive"))
    )
    (net (code "85") (name "Net-(T2-B)") (class "Default")
      (node (ref "R4") (pin "1") (pinfunction "1_1") (pintype "passive"))
      (node (ref "T2") (pin "1") (pinfunction "B_1") (pintype "passive"))
    )
    (net (code "86") (name "Net-(T2-C)") (class "Default")
      (node (ref "R3") (pin "2") (pinfunction "2_2") (pintype "passive"))
      (node (ref "T2") (pin "2") (pinfunction "C_2") (pintype "passive"))
    )
    (net (code "87") (name "Net-(T3-G)") (class "Default")
      (node (ref "R61") (pin "2") (pinfunction "2_2") (pintype "passive"))
      (node (ref "T3") (pin "3") (pinfunction "G_3") (pintype "passive"))
    )
    (net (code "88") (name "Net-(T3-S)") (class "Default")
      (node (ref "R8") (pin "2") (pinfunction "2_2") (pintype "passive"))
      (node (ref "T3") (pin "2") (pinfunction "S_2") (pintype "passive"))
    )
    (net (code "89") (name "Net-(T4-G)") (class "Default")
      (node (ref "R11") (pin "2") (pinfunction "2_2") (pintype "passive"))
      (node (ref "T4") (pin "3") (pinfunction "G_3") (pintype "passive"))
    )
    (net (code "90") (name "Net-(T4-S)") (class "Default")
      (node (ref "R7") (pin "2") (pinfunction "2_2") (pintype "passive"))
      (node (ref "T4") (pin "2") (pinfunction "S_2") (pintype "passive"))
    )
    (net (code "91") (name "Net-(T5-G)") (class "Default")
      (node (ref "R63") (pin "2") (pinfunction "2_2") (pintype "passive"))
      (node (ref "T5") (pin "3") (pinfunction "G_3") (pintype "passive"))
    )
    (net (code "92") (name "Net-(T5-S)") (class "Default")
      (node (ref "R12") (pin "2") (pinfunction "2_2") (pintype "passive"))
      (node (ref "T5") (pin "2") (pinfunction "S_2") (pintype "passive"))
    )
    (net (code "93") (name "Net-(T6-G)") (class "Default")
      (node (ref "R64") (pin "2") (pinfunction "2_2") (pintype "passive"))
      (node (ref "T6") (pin "3") (pinfunction "G_3") (pintype "passive"))
    )
    (net (code "94") (name "Net-(T6-S)") (class "Default")
      (node (ref "R13") (pin "2") (pinfunction "2_2") (pintype "passive"))
      (node (ref "T6") (pin "2") (pinfunction "S_2") (pintype "passive"))
    )
    (net (code "95") (name "unconnected-(IC12-(TDI)PC5-Pad27)") (class "Default")
      (node (ref "IC12") (pin "27") (pinfunction "(TDI)PC5_27") (pintype "bidirectional"))
    )
    (net (code "96") (name "unconnected-(X2-PadG1)") (class "Default")
      (node (ref "X2") (pin "G1") (pinfunction "G1_G1") (pintype "passive"))
    )
    (net (code "97") (name "unconnected-(X2-PadG2)") (class "Default")
      (node (ref "X2") (pin "G2") (pinfunction "G2_G2") (pintype "passive"))
    )
    (net (code "98") (name "unconnected-(X7-UPLINK-Pad7)") (class "Default")
      (node (ref "X7-UPLINK") (pin "7") (pinfunction "7_7") (pintype "passive"))
    )
    (net (code "99") (name "unconnected-(X7-UPLINK-Pad8)") (class "Default")
      (node (ref "X7-UPLINK") (pin "8") (pinfunction "8_8") (pintype "passive"))
    )
  )
)
